# 16-AM64x-05.net
KiCad netlist of a schematic drawn in Altium Designer
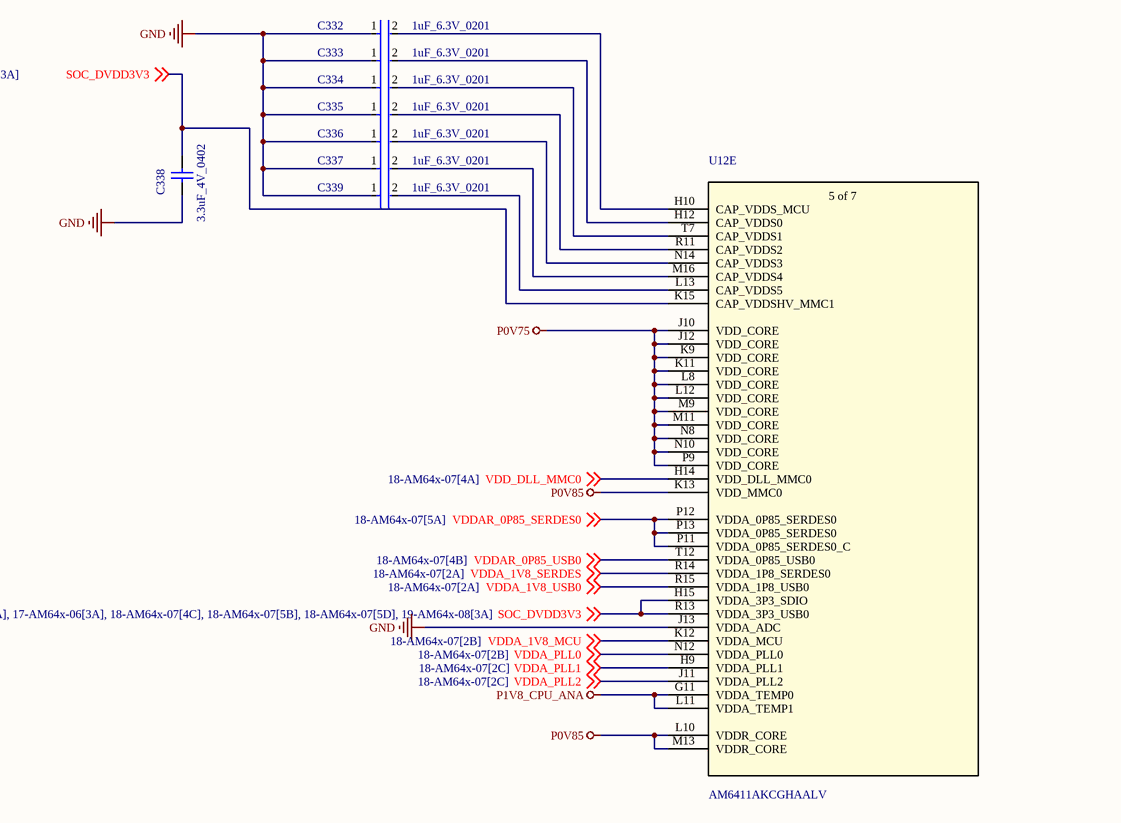
[diagram p0: 16-AM64x-05.SchDoc]

(export (version "E")
  (design (tool "Eeschema 10.0.6"))
  (components
    (comp (ref "C332")
      (value "1uF_6.3V_0201")
      (footprint "FP-CL03-IPC_B")
      (description "Cap Ceramic 1uF 6.3V X5R ±20% Pad SMD 0201 +85°C T/R")
      (fields (field (name "TOLERANCE") "20%"))
      (libsource (lib "Altium Content Vault") (part "b4654b650e69147ec39a6b967a45e02"))
    )
    (comp (ref "C333")
      (value "1uF_6.3V_0201")
      (footprint "FP-CL03-IPC_B")
      (description "Cap Ceramic 1uF 6.3V X5R ±20% Pad SMD 0201 +85°C T/R")
      (fields (field (name "TOLERANCE") "20%"))
      (libsource (lib "Altium Content Vault") (part "b4654b650e69147ec39a6b967a45e02"))
    )
    (comp (ref "C334")
      (value "1uF_6.3V_0201")
      (footprint "FP-CL03-IPC_B")
      (description "Cap Ceramic 1uF 6.3V X5R ±20% Pad SMD 0201 +85°C T/R")
      (fields (field (name "TOLERANCE") "20%"))
      (libsource (lib "Altium Content Vault") (part "b4654b650e69147ec39a6b967a45e02"))
    )
    (comp (ref "C335")
      (value "1uF_6.3V_0201")
      (footprint "FP-CL03-IPC_B")
      (description "Cap Ceramic 1uF 6.3V X5R ±20% Pad SMD 0201 +85°C T/R")
      (fields (field (name "TOLERANCE") "20%"))
      (libsource (lib "Altium Content Vault") (part "b4654b650e69147ec39a6b967a45e02"))
    )
    (comp (ref "C336")
      (value "1uF_6.3V_0201")
      (footprint "FP-CL03-IPC_B")
      (description "Cap Ceramic 1uF 6.3V X5R ±20% Pad SMD 0201 +85°C T/R")
      (fields (field (name "TOLERANCE") "20%"))
      (libsource (lib "Altium Content Vault") (part "b4654b650e69147ec39a6b967a45e02"))
    )
    (comp (ref "C337")
      (value "1uF_6.3V_0201")
      (footprint "FP-CL03-IPC_B")
      (description "Cap Ceramic 1uF 6.3V X5R ±20% Pad SMD 0201 +85°C T/R")
      (fields (field (name "TOLERANCE") "20%"))
      (libsource (lib "Altium Content Vault") (part "b4654b650e69147ec39a6b967a45e02"))
    )
    (comp (ref "C338")
      (value "3.3uF_4V_0402")
      (footprint "CAPC1005X60X30LL05T10")
      (fields (field (name "PART NUMBER") "C0402C335M7PACTU") (field (name "MANUFACTURER") "Kemet"))
      (libsource (lib "Altium Content Vault") (part "CAP"))
    )
    (comp (ref "C339")
      (value "1uF_6.3V_0201")
      (footprint "FP-CL03-IPC_B")
      (description "Cap Ceramic 1uF 6.3V X5R ±20% Pad SMD 0201 +85°C T/R")
      (fields (field (name "TOLERANCE") "20%"))
      (libsource (lib "Altium Content Vault") (part "b4654b650e69147ec39a6b967a45e02"))
    )
    (comp (ref "U12")
      (value "AM6411AKCGHAALV")
      (footprint "FCBGA441_ALV_TEX")
      (description "No Description Available")
      (libsource (lib "AM6411AKCGHAALV") (part "AM6411AKCGHAALV"))
    )
  )
  (nets
    (net (code "1") (name "GND") (class "Default")
      (node (ref "C332") (pin "1") (pinfunction "1_1") (pintype "passive"))
      (node (ref "C333") (pin "1") (pinfunction "1_1") (pintype "passive"))
      (node (ref "C334") (pin "1") (pinfunction "1_1") (pintype "passive"))
      (node (ref "C335") (pin "1") (pinfunction "1_1") (pintype "passive"))
      (node (ref "C336") (pin "1") (pinfunction "1_1") (pintype "passive"))
      (node (ref "C337") (pin "1") (pinfunction "1_1") (pintype "passive"))
      (node (ref "C338") (pin "1") (pinfunction "1_1") (pintype "passive"))
      (node (ref "C339") (pin "1") (pinfunction "1_1") (pintype "passive"))
      (node (ref "U12") (pin "J13") (pinfunction "VDDA_ADC_J13") (pintype "power_in"))
    )
    (net (code "2") (name "Net-(U12E-CAP_VDDS0)") (class "Default")
      (node (ref "C333") (pin "2") (pinfunction "2_2") (pintype "passive"))
      (node (ref "U12") (pin "H12") (pinfunction "CAP_VDDS0_H12") (pintype "power_in"))
    )
    (net (code "3") (name "Net-(U12E-CAP_VDDS1)") (class "Default")
      (node (ref "C334") (pin "2") (pinfunction "2_2") (pintype "passive"))
      (node (ref "U12") (pin "T7") (pinfunction "CAP_VDDS1_T7") (pintype "power_in"))
    )
    (net (code "4") (name "Net-(U12E-CAP_VDDS2)") (class "Default")
      (node (ref "C335") (pin "2") (pinfunction "2_2") (pintype "passive"))
      (node (ref "U12") (pin "R11") (pinfunction "CAP_VDDS2_R11") (pintype "power_in"))
    )
    (net (code "5") (name "Net-(U12E-CAP_VDDS3)") (class "Default")
      (node (ref "C336") (pin "2") (pinfunction "2_2") (pintype "passive"))
      (node (ref "U12") (pin "N14") (pinfunction "CAP_VDDS3_N14") (pintype "power_in"))
    )
    (net (code "6") (name "Net-(U12E-CAP_VDDS4)") (class "Default")
      (node (ref "C337") (pin "2") (pinfunction "2_2") (pintype "passive"))
      (node (ref "U12") (pin "M16") (pinfunction "CAP_VDDS4_M16") (pintype "power_in"))
    )
    (net (code "7") (name "Net-(U12E-CAP_VDDS5)") (class "Default")
      (node (ref "C339") (pin "2") (pinfunction "2_2") (pintype "passive"))
      (node (ref "U12") (pin "L13") (pinfunction "CAP_VDDS5_L13") (pintype "power_in"))
    )
    (net (code "8") (name "Net-(U12E-CAP_VDDS_MCU)") (class "Default")
      (node (ref "C332") (pin "2") (pinfunction "2_2") (pintype "passive"))
      (node (ref "U12") (pin "H10") (pinfunction "CAP_VDDS_MCU_H10") (pintype "power_in"))
    )
    (net (code "9") (name "P0V75") (class "Default")
      (node (ref "U12") (pin "J10") (pinfunction "VDD_CORE_J10") (pintype "power_in"))
      (node (ref "U12") (pin "J12") (pinfunction "VDD_CORE_J12") (pintype "power_in"))
      (node (ref "U12") (pin "K11") (pinfunction "VDD_CORE_K11") (pintype "power_in"))
      (node (ref "U12") (pin "K9") (pinfunction "VDD_CORE_K9") (pintype "power_in"))
      (node (ref "U12") (pin "L12") (pinfunction "VDD_CORE_L12") (pintype "power_in"))
      (node (ref "U12") (pin "L8") (pinfunction "VDD_CORE_L8") (pintype "power_in"))
      (node (ref "U12") (pin "M11") (pinfunction "VDD_CORE_M11") (pintype "power_in"))
      (node (ref "U12") (pin "M9") (pinfunction "VDD_CORE_M9") (pintype "power_in"))
      (node (ref "U12") (pin "N10") (pinfunction "VDD_CORE_N10") (pintype "power_in"))
      (node (ref "U12") (pin "N8") (pinfunction "VDD_CORE_N8") (pintype "power_in"))
      (node (ref "U12") (pin "P9") (pinfunction "VDD_CORE_P9") (pintype "power_in"))
    )
    (net (code "10") (name "P0V85") (class "Default")
      (node (ref "U12") (pin "K13") (pinfunction "VDD_MMC0_K13") (pintype "power_in"))
      (node (ref "U12") (pin "L10") (pinfunction "VDDR_CORE_L10") (pintype "power_in"))
      (node (ref "U12") (pin "M13") (pinfunction "VDDR_CORE_M13") (pintype "power_in"))
    )
    (net (code "11") (name "P1V8_CPU_ANA") (class "Default")
      (node (ref "U12") (pin "G11") (pinfunction "VDDA_TEMP0_G11") (pintype "power_in"))
      (node (ref "U12") (pin "L11") (pinfunction "VDDA_TEMP1_L11") (pintype "power_in"))
    )
    (net (code "12") (name "SOC_DVDD3V3") (class "Default")
      (node (ref "C338") (pin "2") (pinfunction "2_2") (pintype "passive"))
      (node (ref "U12") (pin "H15") (pinfunction "VDDA_3P3_SDIO_H15") (pintype "power_in"))
      (node (ref "U12") (pin "K15") (pinfunction "CAP_VDDSHV_MMC1_K15") (pintype "power_in"))
      (node (ref "U12") (pin "R13") (pinfunction "VDDA_3P3_USB0_R13") (pintype "power_in"))
    )
    (net (code "13") (name "VDDAR_0P85_SERDES0") (class "Default")
      (node (ref "U12") (pin "P11") (pinfunction "VDDA_0P85_SERDES0_C_P11") (pintype "power_in"))
      (node (ref "U12") (pin "P12") (pinfunction "VDDA_0P85_SERDES0_P12") (pintype "power_in"))
      (node (ref "U12") (pin "P13") (pinfunction "VDDA_0P85_SERDES0_P13") (pintype "power_in"))
    )
    (net (code "14") (name "VDDAR_0P85_USB0") (class "Default")
      (node (ref "U12") (pin "T12") (pinfunction "VDDA_0P85_USB0_T12") (pintype "power_in"))
    )
    (net (code "15") (name "VDDA_1V8_MCU") (class "Default")
      (node (ref "U12") (pin "K12") (pinfunction "VDDA_MCU_K12") (pintype "power_in"))
    )
    (net (code "16") (name "VDDA_1V8_SERDES") (class "Default")
      (node (ref "U12") (pin "R14") (pinfunction "VDDA_1P8_SERDES0_R14") (pintype "power_in"))
    )
    (net (code "17") (name "VDDA_1V8_USB0") (class "Default")
      (node (ref "U12") (pin "R15") (pinfunction "VDDA_1P8_USB0_R15") (pintype "power_in"))
    )
    (net (code "18") (name "VDDA_PLL0") (class "Default")
      (node (ref "U12") (pin "N12") (pinfunction "VDDA_PLL0_N12") (pintype "power_in"))
    )
    (net (code "19") (name "VDDA_PLL1") (class "Default")
      (node (ref "U12") (pin "H9") (pinfunction "VDDA_PLL1_H9") (pintype "power_in"))
    )
    (net (code "20") (name "VDDA_PLL2") (class "Default")
      (node (ref "U12") (pin "J11") (pinfunction "VDDA_PLL2_J11") (pintype "power_in"))
    )
    (net (code "21") (name "VDD_DLL_MMC0") (class "Default")
      (node (ref "U12") (pin "H14") (pinfunction "VDD_DLL_MMC0_H14") (pintype "power_in"))
    )
  )
)
